# ESP12F.net
KiCad netlist of a schematic drawn in Altium Designer
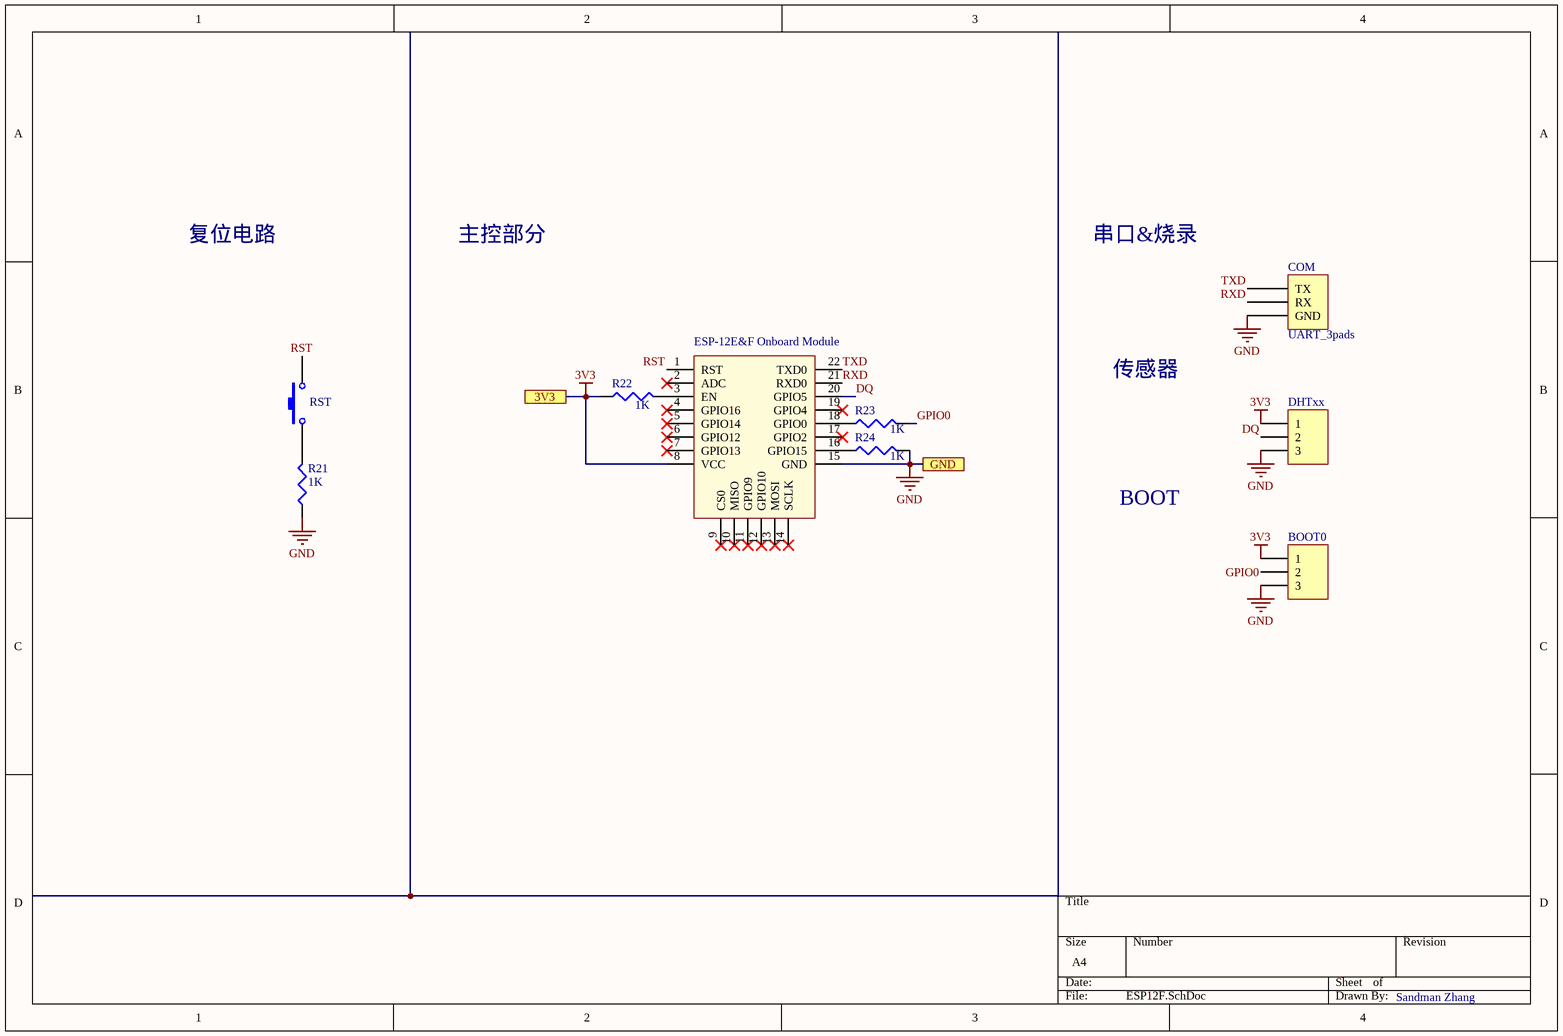
[diagram p0: ESP12F.SchDoc]

(export (version "E")
  (design (tool "Eeschema 10.0.6"))
  (components
    (comp (ref "BOOT0")
      (value "工作")
      (footprint "HDR1X3")
      (description "Header, 3-Pin")
      (fields (field (name "PUBLISHER") "Altium Limited"))
      (libsource (lib "Miscellaneous Connectors") (part "Header 3"))
    )
    (comp (ref "COM")
      (value "UART_3pads")
      (footprint "3pads")
      (libsource (lib "Connectivity_pads") (part "UART_3pads"))
    )
    (comp (ref "DHTxx")
      (value "7")
      (footprint "HDR1X3")
      (description "Header, 3-Pin")
      (fields (field (name "PUBLISHER") "Altium Limited"))
      (libsource (lib "Miscellaneous Connectors") (part "Header 3"))
    )
    (comp (ref "R21")
      (value "1K")
      (footprint "J1-0603")
      (description "Resistor")
      (fields (field (name "Comment") "Res3") (field (name "PUBLISHER") "Altium Limited"))
      (libsource (lib "Miscellaneous Devices") (part "Res3"))
    )
    (comp (ref "R22")
      (value "1K")
      (footprint "J1-0603")
      (description "Resistor")
      (fields (field (name "Comment") "Res3") (field (name "PUBLISHER") "Altium Limited"))
      (libsource (lib "Miscellaneous Devices") (part "Res3"))
    )
    (comp (ref "R23")
      (value "1K")
      (footprint "J1-0603")
      (description "Resistor")
      (fields (field (name "Comment") "Res3") (field (name "PUBLISHER") "Altium Limited"))
      (libsource (lib "Miscellaneous Devices") (part "Res3"))
    )
    (comp (ref "R24")
      (value "1K")
      (footprint "J1-0603")
      (description "Resistor")
      (fields (field (name "Comment") "Res3") (field (name "PUBLISHER") "Altium Limited"))
      (libsource (lib "Miscellaneous Devices") (part "Res3"))
    )
    (comp (ref "RST")
      (value "SW-PB")
      (footprint "SPST-2")
      (description "Switch")
      (fields (field (name "PUBLISHER") "Altium Limited"))
      (libsource (lib "Miscellaneous Devices") (part "SW-PB"))
    )
    (comp (ref "U1")
      (value "ESP-12E&F Onboard Module")
      (footprint "ESP-12E&F Module")
      (libsource (lib "ESP-12E&F Onboard Module") (part "ESP-12E&F Onboard Module"))
    )
  )
  (nets
    (net (code "1") (name "/DQ") (class "Default")
      (node (ref "DHTxx") (pin "2") (pinfunction "2_2") (pintype "passive"))
      (node (ref "U1") (pin "20") (pinfunction "GPIO5_20") (pintype "passive"))
    )
    (net (code "2") (name "/GPIO0") (class "Default")
      (node (ref "BOOT0") (pin "2") (pinfunction "2_2") (pintype "passive"))
      (node (ref "R23") (pin "2") (pinfunction "2_2") (pintype "passive"))
    )
    (net (code "3") (name "/RST") (class "Default")
      (node (ref "RST") (pin "2") (pinfunction "2_2") (pintype "passive"))
      (node (ref "U1") (pin "1") (pinfunction "RST_1") (pintype "passive"))
    )
    (net (code "4") (name "/RXD") (class "Default")
      (node (ref "COM") (pin "1") (pinfunction "RX_1") (pintype "passive"))
      (node (ref "U1") (pin "21") (pinfunction "RXD0_21") (pintype "passive"))
    )
    (net (code "5") (name "/TXD") (class "Default")
      (node (ref "COM") (pin "0") (pinfunction "TX_0") (pintype "passive"))
      (node (ref "U1") (pin "22") (pinfunction "TXD0_22") (pintype "passive"))
    )
    (net (code "6") (name "3V3") (class "Default")
      (node (ref "BOOT0") (pin "1") (pinfunction "1_1") (pintype "passive"))
      (node (ref "DHTxx") (pin "1") (pinfunction "1_1") (pintype "passive"))
      (node (ref "R22") (pin "1") (pinfunction "1_1") (pintype "passive"))
      (node (ref "U1") (pin "8") (pinfunction "VCC_8") (pintype "passive"))
    )
    (net (code "7") (name "GND") (class "Default")
      (node (ref "BOOT0") (pin "3") (pinfunction "3_3") (pintype "passive"))
      (node (ref "COM") (pin "2") (pinfunction "GND_2") (pintype "passive"))
      (node (ref "DHTxx") (pin "3") (pinfunction "3_3") (pintype "passive"))
      (node (ref "R21") (pin "1") (pinfunction "1_1") (pintype "passive"))
      (node (ref "R24") (pin "2") (pinfunction "2_2") (pintype "passive"))
      (node (ref "U1") (pin "15") (pinfunction "GND_15") (pintype "passive"))
    )
    (net (code "8") (name "Net-(R21-Pad2)") (class "Default")
      (node (ref "R21") (pin "2") (pinfunction "2_2") (pintype "passive"))
      (node (ref "RST") (pin "1") (pinfunction "1_1") (pintype "passive"))
    )
    (net (code "9") (name "Net-(U1-EN)") (class "Default")
      (node (ref "R22") (pin "2") (pinfunction "2_2") (pintype "passive"))
      (node (ref "U1") (pin "3") (pinfunction "EN_3") (pintype "passive"))
    )
    (net (code "10") (name "Net-(U1-GPIO0)") (class "Default")
      (node (ref "R23") (pin "1") (pinfunction "1_1") (pintype "passive"))
      (node (ref "U1") (pin "18") (pinfunction "GPIO0_18") (pintype "passive"))
    )
    (net (code "11") (name "Net-(U1-GPIO15)") (class "Default")
      (node (ref "R24") (pin "1") (pinfunction "1_1") (pintype "passive"))
      (node (ref "U1") (pin "16") (pinfunction "GPIO15_16") (pintype "passive"))
    )
    (net (code "12") (name "unconnected-(U1-ADC-Pad2)") (class "Default")
      (node (ref "U1") (pin "2") (pinfunction "ADC_2") (pintype "passive+no_connect"))
    )
    (net (code "13") (name "unconnected-(U1-CS0-Pad9)") (class "Default")
      (node (ref "U1") (pin "9") (pinfunction "CS0_9") (pintype "passive+no_connect"))
    )
    (net (code "14") (name "unconnected-(U1-GPIO2-Pad17)") (class "Default")
      (node (ref "U1") (pin "17") (pinfunction "GPIO2_17") (pintype "passive+no_connect"))
    )
    (net (code "15") (name "unconnected-(U1-GPIO4-Pad19)") (class "Default")
      (node (ref "U1") (pin "19") (pinfunction "GPIO4_19") (pintype "passive+no_connect"))
    )
    (net (code "16") (name "unconnected-(U1-GPIO9-Pad11)") (class "Default")
      (node (ref "U1") (pin "11") (pinfunction "GPIO9_11") (pintype "passive+no_connect"))
    )
    (net (code "17") (name "unconnected-(U1-GPIO10-Pad12)") (class "Default")
      (node (ref "U1") (pin "12") (pinfunction "GPIO10_12") (pintype "passive+no_connect"))
    )
    (net (code "18") (name "unconnected-(U1-GPIO12-Pad6)") (class "Default")
      (node (ref "U1") (pin "6") (pinfunction "GPIO12_6") (pintype "passive+no_connect"))
    )
    (net (code "19") (name "unconnected-(U1-GPIO13-Pad7)") (class "Default")
      (node (ref "U1") (pin "7") (pinfunction "GPIO13_7") (pintype "passive+no_connect"))
    )
    (net (code "20") (name "unconnected-(U1-GPIO14-Pad5)") (class "Default")
      (node (ref "U1") (pin "5") (pinfunction "GPIO14_5") (pintype "passive+no_connect"))
    )
    (net (code "21") (name "unconnected-(U1-GPIO16-Pad4)") (class "Default")
      (node (ref "U1") (pin "4") (pinfunction "GPIO16_4") (pintype "passive+no_connect"))
    )
    (net (code "22") (name "unconnected-(U1-MISO-Pad10)") (class "Default")
      (node (ref "U1") (pin "10") (pinfunction "MISO_10") (pintype "passive+no_connect"))
    )
    (net (code "23") (name "unconnected-(U1-MOSI-Pad13)") (class "Default")
      (node (ref "U1") (pin "13") (pinfunction "MOSI_13") (pintype "passive+no_connect"))
    )
    (net (code "24") (name "unconnected-(U1-SCLK-Pad14)") (class "Default")
      (node (ref "U1") (pin "14") (pinfunction "SCLK_14") (pintype "passive+no_connect"))
    )
  )
)
